# FPGA.net
KiCad netlist of a schematic drawn in Altium Designer
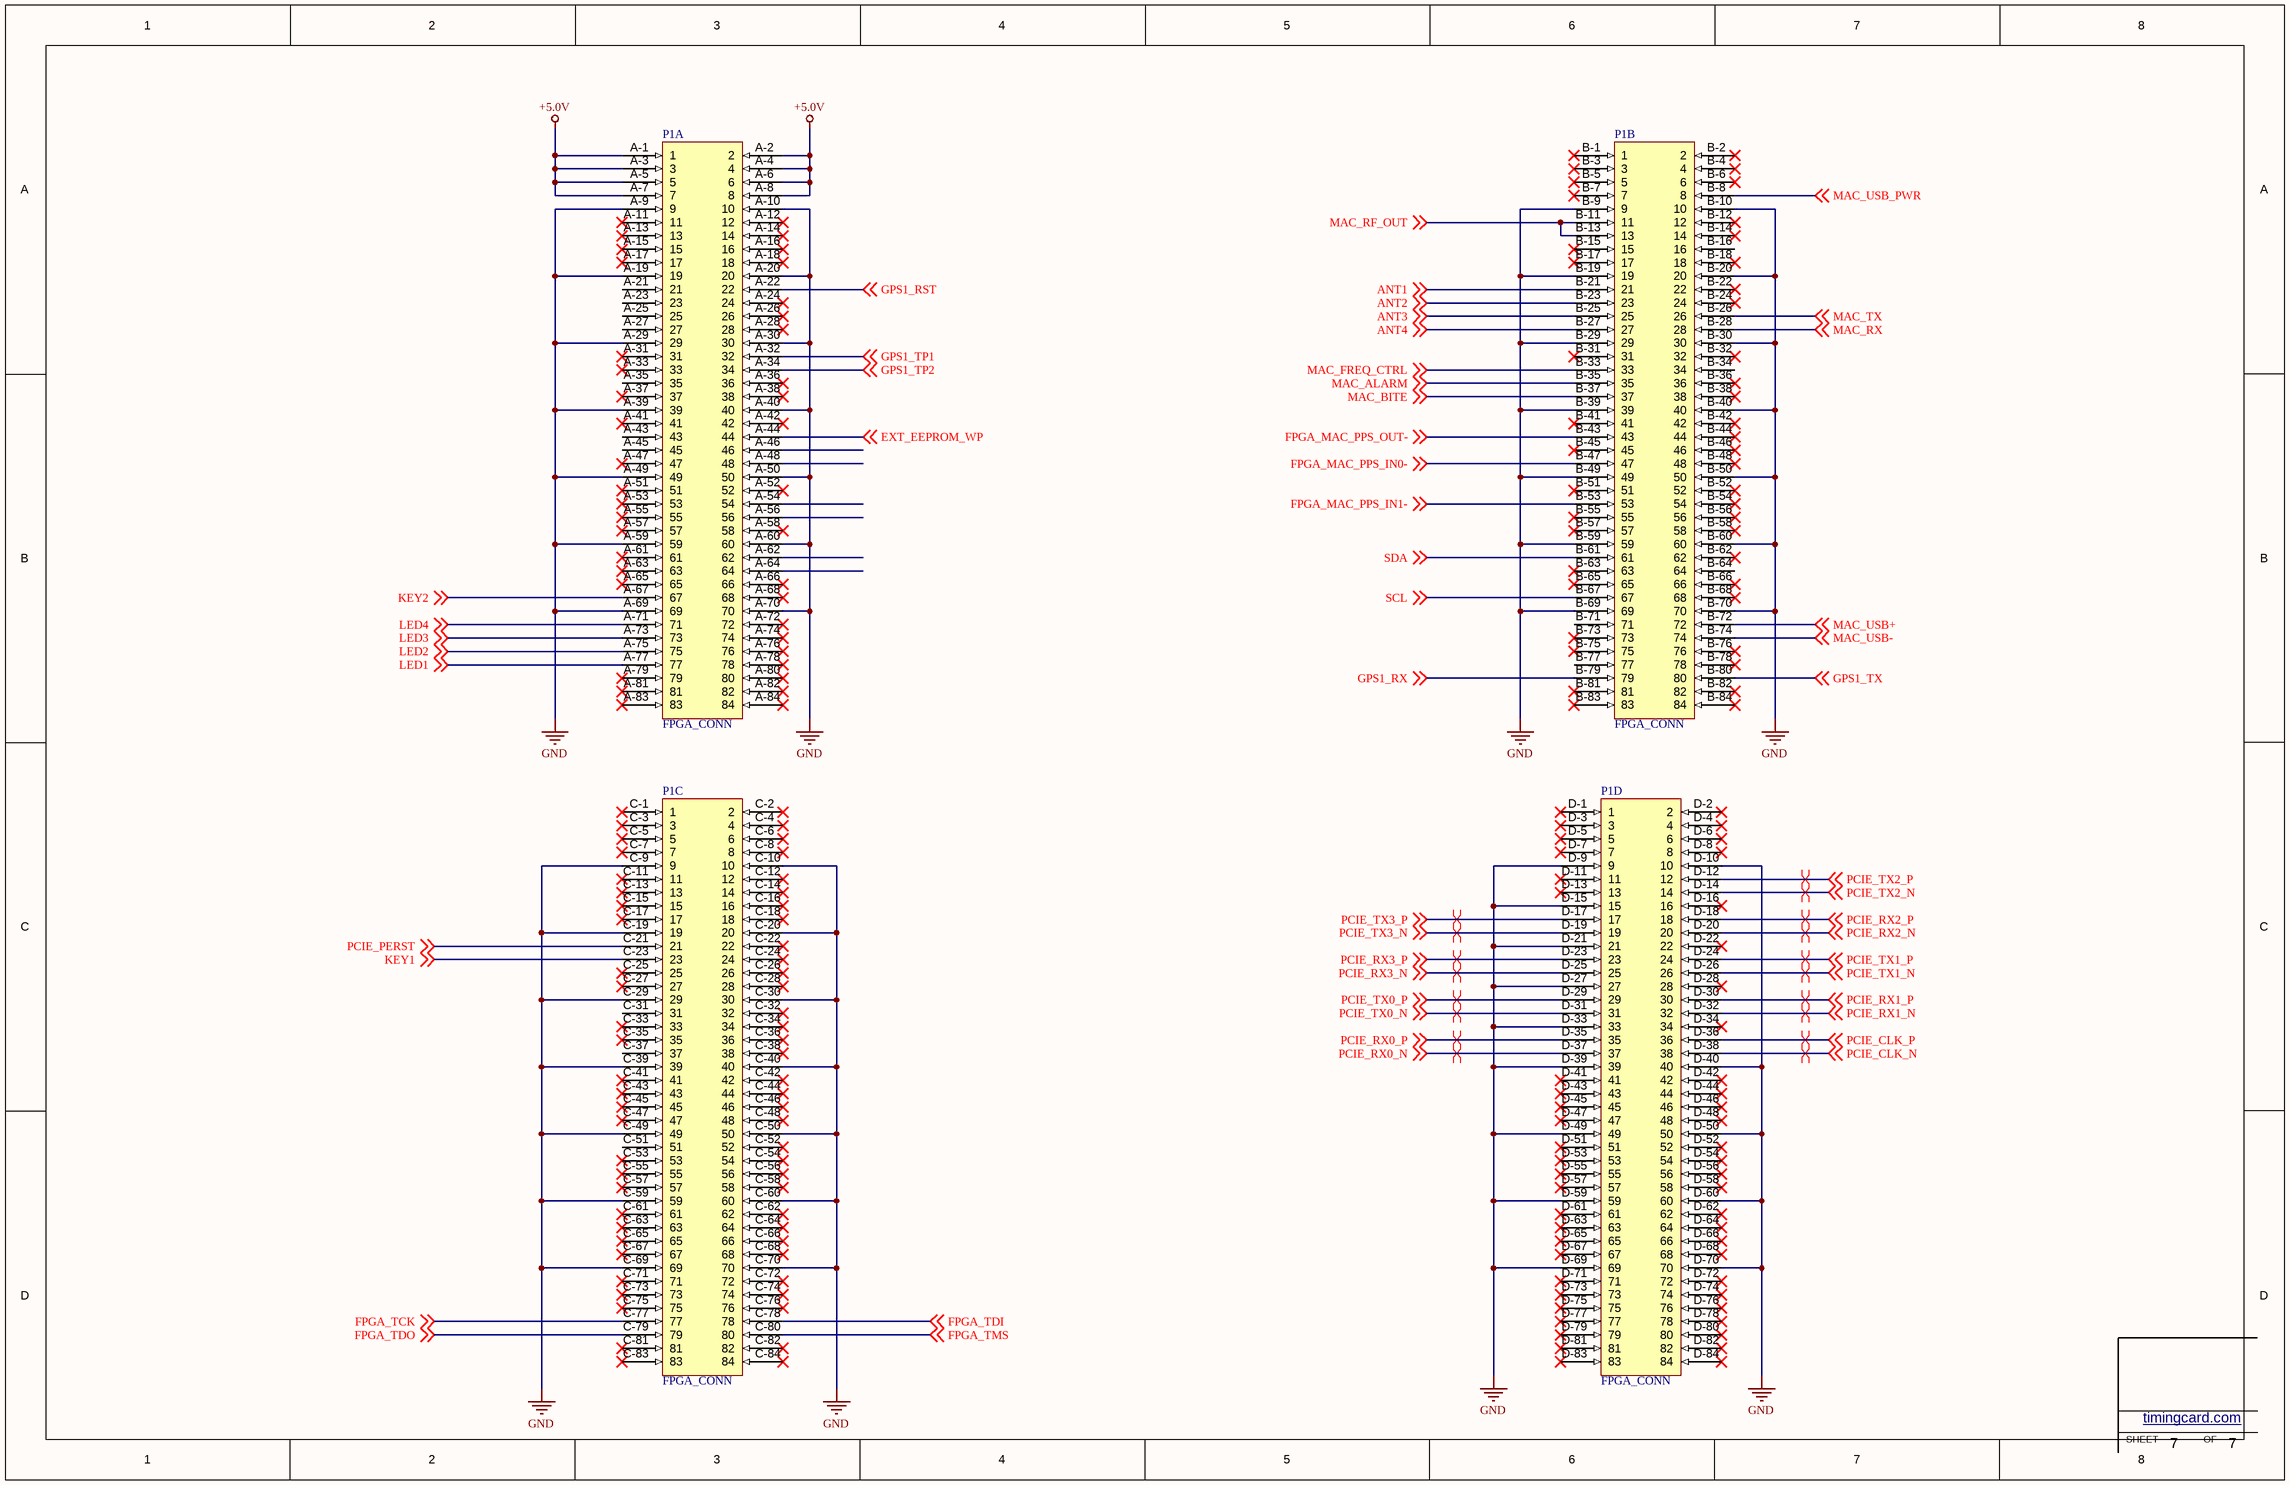
[diagram p0: FPGA.SchDoc]

(export (version "E")
  (design (tool "Eeschema 10.0.6"))
  (components
    (comp (ref "P1")
      (value "FPGA_CONN")
      (footprint "FPGA_CONN")
      (libsource (lib "FPGA_CONN") (part "FPGA_CONN"))
    )
  )
  (nets
    (net (code "1") (name "+5.0V") (class "Default")
      (node (ref "P1") (pin "A-1") (pinfunction "1_A-1") (pintype "input"))
      (node (ref "P1") (pin "A-2") (pinfunction "2_A-2") (pintype "input"))
      (node (ref "P1") (pin "A-3") (pinfunction "3_A-3") (pintype "input"))
      (node (ref "P1") (pin "A-4") (pinfunction "4_A-4") (pintype "input"))
      (node (ref "P1") (pin "A-5") (pinfunction "5_A-5") (pintype "input"))
      (node (ref "P1") (pin "A-6") (pinfunction "6_A-6") (pintype "input"))
      (node (ref "P1") (pin "A-7") (pinfunction "7_A-7") (pintype "input"))
      (node (ref "P1") (pin "A-8") (pinfunction "8_A-8") (pintype "input"))
    )
    (net (code "2") (name "ANT1") (class "Default")
      (node (ref "P1") (pin "B-21") (pinfunction "21_B-21") (pintype "input"))
    )
    (net (code "3") (name "ANT2") (class "Default")
      (node (ref "P1") (pin "B-23") (pinfunction "23_B-23") (pintype "input"))
    )
    (net (code "4") (name "ANT3") (class "Default")
      (node (ref "P1") (pin "B-25") (pinfunction "25_B-25") (pintype "input"))
    )
    (net (code "5") (name "ANT4") (class "Default")
      (node (ref "P1") (pin "B-27") (pinfunction "27_B-27") (pintype "input"))
    )
    (net (code "6") (name "EXT_EEPROM_WP") (class "Default")
      (node (ref "P1") (pin "A-44") (pinfunction "44_A-44") (pintype "input"))
    )
    (net (code "7") (name "FPGA_MAC_PPS_IN0-") (class "Default")
      (node (ref "P1") (pin "B-47") (pinfunction "47_B-47") (pintype "input"))
    )
    (net (code "8") (name "FPGA_MAC_PPS_IN1-") (class "Default")
      (node (ref "P1") (pin "B-53") (pinfunction "53_B-53") (pintype "input"))
    )
    (net (code "9") (name "FPGA_MAC_PPS_OUT-") (class "Default")
      (node (ref "P1") (pin "B-43") (pinfunction "43_B-43") (pintype "input"))
    )
    (net (code "10") (name "FPGA_TCK") (class "Default")
      (node (ref "P1") (pin "C-77") (pinfunction "77_C-77") (pintype "input"))
    )
    (net (code "11") (name "FPGA_TDI") (class "Default")
      (node (ref "P1") (pin "C-78") (pinfunction "78_C-78") (pintype "input"))
    )
    (net (code "12") (name "FPGA_TDO") (class "Default")
      (node (ref "P1") (pin "C-79") (pinfunction "79_C-79") (pintype "input"))
    )
    (net (code "13") (name "FPGA_TMS") (class "Default")
      (node (ref "P1") (pin "C-80") (pinfunction "80_C-80") (pintype "input"))
    )
    (net (code "14") (name "GND") (class "Default")
      (node (ref "P1") (pin "A-10") (pinfunction "10_A-10") (pintype "input"))
      (node (ref "P1") (pin "A-19") (pinfunction "19_A-19") (pintype "input"))
      (node (ref "P1") (pin "A-20") (pinfunction "20_A-20") (pintype "input"))
      (node (ref "P1") (pin "A-29") (pinfunction "29_A-29") (pintype "input"))
      (node (ref "P1") (pin "A-30") (pinfunction "30_A-30") (pintype "input"))
      (node (ref "P1") (pin "A-39") (pinfunction "39_A-39") (pintype "input"))
      (node (ref "P1") (pin "A-40") (pinfunction "40_A-40") (pintype "input"))
      (node (ref "P1") (pin "A-49") (pinfunction "49_A-49") (pintype "input"))
      (node (ref "P1") (pin "A-50") (pinfunction "50_A-50") (pintype "input"))
      (node (ref "P1") (pin "A-59") (pinfunction "59_A-59") (pintype "input"))
      (node (ref "P1") (pin "A-60") (pinfunction "60_A-60") (pintype "input"))
      (node (ref "P1") (pin "A-69") (pinfunction "69_A-69") (pintype "input"))
      (node (ref "P1") (pin "A-70") (pinfunction "70_A-70") (pintype "input"))
      (node (ref "P1") (pin "A-9") (pinfunction "9_A-9") (pintype "input"))
      (node (ref "P1") (pin "B-10") (pinfunction "10_B-10") (pintype "input"))
      (node (ref "P1") (pin "B-19") (pinfunction "19_B-19") (pintype "input"))
      (node (ref "P1") (pin "B-20") (pinfunction "20_B-20") (pintype "input"))
      (node (ref "P1") (pin "B-29") (pinfunction "29_B-29") (pintype "input"))
      (node (ref "P1") (pin "B-30") (pinfunction "30_B-30") (pintype "input"))
      (node (ref "P1") (pin "B-39") (pinfunction "39_B-39") (pintype "input"))
      (node (ref "P1") (pin "B-40") (pinfunction "40_B-40") (pintype "input"))
      (node (ref "P1") (pin "B-49") (pinfunction "49_B-49") (pintype "input"))
      (node (ref "P1") (pin "B-50") (pinfunction "50_B-50") (pintype "input"))
      (node (ref "P1") (pin "B-59") (pinfunction "59_B-59") (pintype "input"))
      (node (ref "P1") (pin "B-60") (pinfunction "60_B-60") (pintype "input"))
      (node (ref "P1") (pin "B-69") (pinfunction "69_B-69") (pintype "input"))
      (node (ref "P1") (pin "B-70") (pinfunction "70_B-70") (pintype "input"))
      (node (ref "P1") (pin "B-9") (pinfunction "9_B-9") (pintype "input"))
      (node (ref "P1") (pin "C-10") (pinfunction "10_C-10") (pintype "input"))
      (node (ref "P1") (pin "C-19") (pinfunction "19_C-19") (pintype "input"))
      (node (ref "P1") (pin "C-20") (pinfunction "20_C-20") (pintype "input"))
      (node (ref "P1") (pin "C-29") (pinfunction "29_C-29") (pintype "input"))
      (node (ref "P1") (pin "C-30") (pinfunction "30_C-30") (pintype "input"))
      (node (ref "P1") (pin "C-39") (pinfunction "39_C-39") (pintype "input"))
      (node (ref "P1") (pin "C-40") (pinfunction "40_C-40") (pintype "input"))
      (node (ref "P1") (pin "C-49") (pinfunction "49_C-49") (pintype "input"))
      (node (ref "P1") (pin "C-50") (pinfunction "50_C-50") (pintype "input"))
      (node (ref "P1") (pin "C-59") (pinfunction "59_C-59") (pintype "input"))
      (node (ref "P1") (pin "C-60") (pinfunction "60_C-60") (pintype "input"))
      (node (ref "P1") (pin "C-69") (pinfunction "69_C-69") (pintype "input"))
      (node (ref "P1") (pin "C-70") (pinfunction "70_C-70") (pintype "input"))
      (node (ref "P1") (pin "C-9") (pinfunction "9_C-9") (pintype "input"))
      (node (ref "P1") (pin "D-10") (pinfunction "10_D-10") (pintype "input"))
      (node (ref "P1") (pin "D-15") (pinfunction "15_D-15") (pintype "input"))
      (node (ref "P1") (pin "D-21") (pinfunction "21_D-21") (pintype "input"))
      (node (ref "P1") (pin "D-27") (pinfunction "27_D-27") (pintype "input"))
      (node (ref "P1") (pin "D-33") (pinfunction "33_D-33") (pintype "input"))
      (node (ref "P1") (pin "D-39") (pinfunction "39_D-39") (pintype "input"))
      (node (ref "P1") (pin "D-40") (pinfunction "40_D-40") (pintype "input"))
      (node (ref "P1") (pin "D-49") (pinfunction "49_D-49") (pintype "input"))
      (node (ref "P1") (pin "D-50") (pinfunction "50_D-50") (pintype "input"))
      (node (ref "P1") (pin "D-59") (pinfunction "59_D-59") (pintype "input"))
      (node (ref "P1") (pin "D-60") (pinfunction "60_D-60") (pintype "input"))
      (node (ref "P1") (pin "D-69") (pinfunction "69_D-69") (pintype "input"))
      (node (ref "P1") (pin "D-70") (pinfunction "70_D-70") (pintype "input"))
      (node (ref "P1") (pin "D-9") (pinfunction "9_D-9") (pintype "input"))
    )
    (net (code "15") (name "GPS1_RST") (class "Default")
      (node (ref "P1") (pin "A-22") (pinfunction "22_A-22") (pintype "input"))
    )
    (net (code "16") (name "GPS1_RX") (class "Default")
      (node (ref "P1") (pin "B-79") (pinfunction "79_B-79") (pintype "input"))
    )
    (net (code "17") (name "GPS1_TP1") (class "Default")
      (node (ref "P1") (pin "A-32") (pinfunction "32_A-32") (pintype "input"))
    )
    (net (code "18") (name "GPS1_TP2") (class "Default")
      (node (ref "P1") (pin "A-34") (pinfunction "34_A-34") (pintype "input"))
    )
    (net (code "19") (name "GPS1_TX") (class "Default")
      (node (ref "P1") (pin "B-80") (pinfunction "80_B-80") (pintype "input"))
    )
    (net (code "20") (name "KEY1") (class "Default")
      (node (ref "P1") (pin "C-23") (pinfunction "23_C-23") (pintype "input"))
    )
    (net (code "21") (name "KEY2") (class "Default")
      (node (ref "P1") (pin "A-67") (pinfunction "67_A-67") (pintype "input"))
    )
    (net (code "22") (name "LED1") (class "Default")
      (node (ref "P1") (pin "A-77") (pinfunction "77_A-77") (pintype "input"))
    )
    (net (code "23") (name "LED2") (class "Default")
      (node (ref "P1") (pin "A-75") (pinfunction "75_A-75") (pintype "input"))
    )
    (net (code "24") (name "LED3") (class "Default")
      (node (ref "P1") (pin "A-73") (pinfunction "73_A-73") (pintype "input"))
    )
    (net (code "25") (name "LED4") (class "Default")
      (node (ref "P1") (pin "A-71") (pinfunction "71_A-71") (pintype "input"))
    )
    (net (code "26") (name "MAC_ALARM") (class "Default")
      (node (ref "P1") (pin "B-35") (pinfunction "35_B-35") (pintype "input"))
    )
    (net (code "27") (name "MAC_BITE") (class "Default")
      (node (ref "P1") (pin "B-37") (pinfunction "37_B-37") (pintype "input"))
    )
    (net (code "28") (name "MAC_FREQ_CTRL") (class "Default")
      (node (ref "P1") (pin "B-33") (pinfunction "33_B-33") (pintype "input"))
    )
    (net (code "29") (name "MAC_RF_OUT") (class "Default")
      (node (ref "P1") (pin "B-11") (pinfunction "11_B-11") (pintype "input"))
      (node (ref "P1") (pin "B-13") (pinfunction "13_B-13") (pintype "input"))
    )
    (net (code "30") (name "MAC_RX") (class "Default")
      (node (ref "P1") (pin "B-28") (pinfunction "28_B-28") (pintype "input"))
    )
    (net (code "31") (name "MAC_TX") (class "Default")
      (node (ref "P1") (pin "B-26") (pinfunction "26_B-26") (pintype "input"))
    )
    (net (code "32") (name "MAC_USB+") (class "Default")
      (node (ref "P1") (pin "B-72") (pinfunction "72_B-72") (pintype "input"))
    )
    (net (code "33") (name "MAC_USB-") (class "Default")
      (node (ref "P1") (pin "B-74") (pinfunction "74_B-74") (pintype "input"))
    )
    (net (code "34") (name "MAC_USB_PWR") (class "Default")
      (node (ref "P1") (pin "B-8") (pinfunction "8_B-8") (pintype "input"))
    )
    (net (code "35") (name "PCIE_CLK_N") (class "Default")
      (node (ref "P1") (pin "D-38") (pinfunction "38_D-38") (pintype "input"))
    )
    (net (code "36") (name "PCIE_CLK_P") (class "Default")
      (node (ref "P1") (pin "D-36") (pinfunction "36_D-36") (pintype "input"))
    )
    (net (code "37") (name "PCIE_PERST") (class "Default")
      (node (ref "P1") (pin "C-21") (pinfunction "21_C-21") (pintype "input"))
    )
    (net (code "38") (name "PCIE_RX0_N") (class "Default")
      (node (ref "P1") (pin "D-37") (pinfunction "37_D-37") (pintype "input"))
    )
    (net (code "39") (name "PCIE_RX0_P") (class "Default")
      (node (ref "P1") (pin "D-35") (pinfunction "35_D-35") (pintype "input"))
    )
    (net (code "40") (name "PCIE_RX1_N") (class "Default")
      (node (ref "P1") (pin "D-32") (pinfunction "32_D-32") (pintype "input"))
    )
    (net (code "41") (name "PCIE_RX1_P") (class "Default")
      (node (ref "P1") (pin "D-30") (pinfunction "30_D-30") (pintype "input"))
    )
    (net (code "42") (name "PCIE_RX2_N") (class "Default")
      (node (ref "P1") (pin "D-20") (pinfunction "20_D-20") (pintype "input"))
    )
    (net (code "43") (name "PCIE_RX2_P") (class "Default")
      (node (ref "P1") (pin "D-18") (pinfunction "18_D-18") (pintype "input"))
    )
    (net (code "44") (name "PCIE_RX3_N") (class "Default")
      (node (ref "P1") (pin "D-25") (pinfunction "25_D-25") (pintype "input"))
    )
    (net (code "45") (name "PCIE_RX3_P") (class "Default")
      (node (ref "P1") (pin "D-23") (pinfunction "23_D-23") (pintype "input"))
    )
    (net (code "46") (name "PCIE_TX0_N") (class "Default")
      (node (ref "P1") (pin "D-31") (pinfunction "31_D-31") (pintype "input"))
    )
    (net (code "47") (name "PCIE_TX0_P") (class "Default")
      (node (ref "P1") (pin "D-29") (pinfunction "29_D-29") (pintype "input"))
    )
    (net (code "48") (name "PCIE_TX1_N") (class "Default")
      (node (ref "P1") (pin "D-26") (pinfunction "26_D-26") (pintype "input"))
    )
    (net (code "49") (name "PCIE_TX1_P") (class "Default")
      (node (ref "P1") (pin "D-24") (pinfunction "24_D-24") (pintype "input"))
    )
    (net (code "50") (name "PCIE_TX2_N") (class "Default")
      (node (ref "P1") (pin "D-14") (pinfunction "14_D-14") (pintype "input"))
    )
    (net (code "51") (name "PCIE_TX2_P") (class "Default")
      (node (ref "P1") (pin "D-12") (pinfunction "12_D-12") (pintype "input"))
    )
    (net (code "52") (name "PCIE_TX3_N") (class "Default")
      (node (ref "P1") (pin "D-19") (pinfunction "19_D-19") (pintype "input"))
    )
    (net (code "53") (name "PCIE_TX3_P") (class "Default")
      (node (ref "P1") (pin "D-17") (pinfunction "17_D-17") (pintype "input"))
    )
    (net (code "54") (name "SCL") (class "Default")
      (node (ref "P1") (pin "B-67") (pinfunction "67_B-67") (pintype "input"))
    )
    (net (code "55") (name "SDA") (class "Default")
      (node (ref "P1") (pin "B-61") (pinfunction "61_B-61") (pintype "input"))
    )
    (net (code "56") (name "unconnected-(P1A-11-PadA-11)") (class "Default")
      (node (ref "P1") (pin "A-11") (pinfunction "11_A-11") (pintype "input+no_connect"))
    )
    (net (code "57") (name "unconnected-(P1A-12-PadA-12)") (class "Default")
      (node (ref "P1") (pin "A-12") (pinfunction "12_A-12") (pintype "input+no_connect"))
    )
    (net (code "58") (name "unconnected-(P1A-13-PadA-13)") (class "Default")
      (node (ref "P1") (pin "A-13") (pinfunction "13_A-13") (pintype "input+no_connect"))
    )
    (net (code "59") (name "unconnected-(P1A-14-PadA-14)") (class "Default")
      (node (ref "P1") (pin "A-14") (pinfunction "14_A-14") (pintype "input+no_connect"))
    )
    (net (code "60") (name "unconnected-(P1A-15-PadA-15)") (class "Default")
      (node (ref "P1") (pin "A-15") (pinfunction "15_A-15") (pintype "input+no_connect"))
    )
    (net (code "61") (name "unconnected-(P1A-16-PadA-16)") (class "Default")
      (node (ref "P1") (pin "A-16") (pinfunction "16_A-16") (pintype "input+no_connect"))
    )
    (net (code "62") (name "unconnected-(P1A-17-PadA-17)") (class "Default")
      (node (ref "P1") (pin "A-17") (pinfunction "17_A-17") (pintype "input+no_connect"))
    )
    (net (code "63") (name "unconnected-(P1A-18-PadA-18)") (class "Default")
      (node (ref "P1") (pin "A-18") (pinfunction "18_A-18") (pintype "input+no_connect"))
    )
    (net (code "64") (name "unconnected-(P1A-21-PadA-21)") (class "Default")
      (node (ref "P1") (pin "A-21") (pinfunction "21_A-21") (pintype "input"))
    )
    (net (code "65") (name "unconnected-(P1A-23-PadA-23)") (class "Default")
      (node (ref "P1") (pin "A-23") (pinfunction "23_A-23") (pintype "input"))
    )
    (net (code "66") (name "unconnected-(P1A-24-PadA-24)") (class "Default")
      (node (ref "P1") (pin "A-24") (pinfunction "24_A-24") (pintype "input+no_connect"))
    )
    (net (code "67") (name "unconnected-(P1A-25-PadA-25)") (class "Default")
      (node (ref "P1") (pin "A-25") (pinfunction "25_A-25") (pintype "input"))
    )
    (net (code "68") (name "unconnected-(P1A-26-PadA-26)") (class "Default")
      (node (ref "P1") (pin "A-26") (pinfunction "26_A-26") (pintype "input+no_connect"))
    )
    (net (code "69") (name "unconnected-(P1A-27-PadA-27)") (class "Default")
      (node (ref "P1") (pin "A-27") (pinfunction "27_A-27") (pintype "input"))
    )
    (net (code "70") (name "unconnected-(P1A-28-PadA-28)") (class "Default")
      (node (ref "P1") (pin "A-28") (pinfunction "28_A-28") (pintype "input+no_connect"))
    )
    (net (code "71") (name "unconnected-(P1A-31-PadA-31)") (class "Default")
      (node (ref "P1") (pin "A-31") (pinfunction "31_A-31") (pintype "input+no_connect"))
    )
    (net (code "72") (name "unconnected-(P1A-33-PadA-33)") (class "Default")
      (node (ref "P1") (pin "A-33") (pinfunction "33_A-33") (pintype "input+no_connect"))
    )
    (net (code "73") (name "unconnected-(P1A-35-PadA-35)") (class "Default")
      (node (ref "P1") (pin "A-35") (pinfunction "35_A-35") (pintype "input"))
    )
    (net (code "74") (name "unconnected-(P1A-36-PadA-36)") (class "Default")
      (node (ref "P1") (pin "A-36") (pinfunction "36_A-36") (pintype "input+no_connect"))
    )
    (net (code "75") (name "unconnected-(P1A-37-PadA-37)") (class "Default")
      (node (ref "P1") (pin "A-37") (pinfunction "37_A-37") (pintype "input+no_connect"))
    )
    (net (code "76") (name "unconnected-(P1A-38-PadA-38)") (class "Default")
      (node (ref "P1") (pin "A-38") (pinfunction "38_A-38") (pintype "input+no_connect"))
    )
    (net (code "77") (name "unconnected-(P1A-41-PadA-41)") (class "Default")
      (node (ref "P1") (pin "A-41") (pinfunction "41_A-41") (pintype "input+no_connect"))
    )
    (net (code "78") (name "unconnected-(P1A-42-PadA-42)") (class "Default")
      (node (ref "P1") (pin "A-42") (pinfunction "42_A-42") (pintype "input+no_connect"))
    )
    (net (code "79") (name "unconnected-(P1A-43-PadA-43)") (class "Default")
      (node (ref "P1") (pin "A-43") (pinfunction "43_A-43") (pintype "input"))
    )
    (net (code "80") (name "unconnected-(P1A-45-PadA-45)") (class "Default")
      (node (ref "P1") (pin "A-45") (pinfunction "45_A-45") (pintype "input"))
    )
    (net (code "81") (name "unconnected-(P1A-46-PadA-46)") (class "Default")
      (node (ref "P1") (pin "A-46") (pinfunction "46_A-46") (pintype "input"))
    )
    (net (code "82") (name "unconnected-(P1A-47-PadA-47)") (class "Default")
      (node (ref "P1") (pin "A-47") (pinfunction "47_A-47") (pintype "input+no_connect"))
    )
    (net (code "83") (name "unconnected-(P1A-48-PadA-48)") (class "Default")
      (node (ref "P1") (pin "A-48") (pinfunction "48_A-48") (pintype "input"))
    )
    (net (code "84") (name "unconnected-(P1A-51-PadA-51)") (class "Default")
      (node (ref "P1") (pin "A-51") (pinfunction "51_A-51") (pintype "input+no_connect"))
    )
    (net (code "85") (name "unconnected-(P1A-52-PadA-52)") (class "Default")
      (node (ref "P1") (pin "A-52") (pinfunction "52_A-52") (pintype "input+no_connect"))
    )
    (net (code "86") (name "unconnected-(P1A-53-PadA-53)") (class "Default")
      (node (ref "P1") (pin "A-53") (pinfunction "53_A-53") (pintype "input+no_connect"))
    )
    (net (code "87") (name "unconnected-(P1A-54-PadA-54)") (class "Default")
      (node (ref "P1") (pin "A-54") (pinfunction "54_A-54") (pintype "input"))
    )
    (net (code "88") (name "unconnected-(P1A-55-PadA-55)") (class "Default")
      (node (ref "P1") (pin "A-55") (pinfunction "55_A-55") (pintype "input+no_connect"))
    )
    (net (code "89") (name "unconnected-(P1A-56-PadA-56)") (class "Default")
      (node (ref "P1") (pin "A-56") (pinfunction "56_A-56") (pintype "input"))
    )
    (net (code "90") (name "unconnected-(P1A-57-PadA-57)") (class "Default")
      (node (ref "P1") (pin "A-57") (pinfunction "57_A-57") (pintype "input+no_connect"))
    )
    (net (code "91") (name "unconnected-(P1A-58-PadA-58)") (class "Default")
      (node (ref "P1") (pin "A-58") (pinfunction "58_A-58") (pintype "input+no_connect"))
    )
    (net (code "92") (name "unconnected-(P1A-61-PadA-61)") (class "Default")
      (node (ref "P1") (pin "A-61") (pinfunction "61_A-61") (pintype "input+no_connect"))
    )
    (net (code "93") (name "unconnected-(P1A-62-PadA-62)") (class "Default")
      (node (ref "P1") (pin "A-62") (pinfunction "62_A-62") (pintype "input"))
    )
    (net (code "94") (name "unconnected-(P1A-63-PadA-63)") (class "Default")
      (node (ref "P1") (pin "A-63") (pinfunction "63_A-63") (pintype "input+no_connect"))
    )
    (net (code "95") (name "unconnected-(P1A-64-PadA-64)") (class "Default")
      (node (ref "P1") (pin "A-64") (pinfunction "64_A-64") (pintype "input"))
    )
    (net (code "96") (name "unconnected-(P1A-65-PadA-65)") (class "Default")
      (node (ref "P1") (pin "A-65") (pinfunction "65_A-65") (pintype "input+no_connect"))
    )
    (net (code "97") (name "unconnected-(P1A-66-PadA-66)") (class "Default")
      (node (ref "P1") (pin "A-66") (pinfunction "66_A-66") (pintype "input+no_connect"))
    )
    (net (code "98") (name "unconnected-(P1A-68-PadA-68)") (class "Default")
      (node (ref "P1") (pin "A-68") (pinfunction "68_A-68") (pintype "input+no_connect"))
    )
    (net (code "99") (name "unconnected-(P1A-72-PadA-72)") (class "Default")
      (node (ref "P1") (pin "A-72") (pinfunction "72_A-72") (pintype "input+no_connect"))
    )
    (net (code "100") (name "unconnected-(P1A-74-PadA-74)") (class "Default")
      (node (ref "P1") (pin "A-74") (pinfunction "74_A-74") (pintype "input+no_connect"))
    )
    (net (code "101") (name "unconnected-(P1A-76-PadA-76)") (class "Default")
      (node (ref "P1") (pin "A-76") (pinfunction "76_A-76") (pintype "input+no_connect"))
    )
    (net (code "102") (name "unconnected-(P1A-78-PadA-78)") (class "Default")
      (node (ref "P1") (pin "A-78") (pinfunction "78_A-78") (pintype "input+no_connect"))
    )
    (net (code "103") (name "unconnected-(P1A-79-PadA-79)") (class "Default")
      (node (ref "P1") (pin "A-79") (pinfunction "79_A-79") (pintype "input+no_connect"))
    )
    (net (code "104") (name "unconnected-(P1A-80-PadA-80)") (class "Default")
      (node (ref "P1") (pin "A-80") (pinfunction "80_A-80") (pintype "input+no_connect"))
    )
    (net (code "105") (name "unconnected-(P1A-81-PadA-81)") (class "Default")
      (node (ref "P1") (pin "A-81") (pinfunction "81_A-81") (pintype "input+no_connect"))
    )
    (net (code "106") (name "unconnected-(P1A-82-PadA-82)") (class "Default")
      (node (ref "P1") (pin "A-82") (pinfunction "82_A-82") (pintype "input+no_connect"))
    )
    (net (code "107") (name "unconnected-(P1A-83-PadA-83)") (class "Default")
      (node (ref "P1") (pin "A-83") (pinfunction "83_A-83") (pintype "input+no_connect"))
    )
    (net (code "108") (name "unconnected-(P1A-84-PadA-84)") (class "Default")
      (node (ref "P1") (pin "A-84") (pinfunction "84_A-84") (pintype "input+no_connect"))
    )
    (net (code "109") (name "unconnected-(P1B-1-PadB-1)") (class "Default")
      (node (ref "P1") (pin "B-1") (pinfunction "1_B-1") (pintype "input+no_connect"))
    )
    (net (code "110") (name "unconnected-(P1B-2-PadB-2)") (class "Default")
      (node (ref "P1") (pin "B-2") (pinfunction "2_B-2") (pintype "input+no_connect"))
    )
    (net (code "111") (name "unconnected-(P1B-3-PadB-3)") (class "Default")
      (node (ref "P1") (pin "B-3") (pinfunction "3_B-3") (pintype "input+no_connect"))
    )
    (net (code "112") (name "unconnected-(P1B-4-PadB-4)") (class "Default")
      (node (ref "P1") (pin "B-4") (pinfunction "4_B-4") (pintype "input+no_connect"))
    )
    (net (code "113") (name "unconnected-(P1B-5-PadB-5)") (class "Default")
      (node (ref "P1") (pin "B-5") (pinfunction "5_B-5") (pintype "input+no_connect"))
    )
    (net (code "114") (name "unconnected-(P1B-6-PadB-6)") (class "Default")
      (node (ref "P1") (pin "B-6") (pinfunction "6_B-6") (pintype "input+no_connect"))
    )
    (net (code "115") (name "unconnected-(P1B-7-PadB-7)") (class "Default")
      (node (ref "P1") (pin "B-7") (pinfunction "7_B-7") (pintype "input+no_connect"))
    )
    (net (code "116") (name "unconnected-(P1B-12-PadB-12)") (class "Default")
      (node (ref "P1") (pin "B-12") (pinfunction "12_B-12") (pintype "input+no_connect"))
    )
    (net (code "117") (name "unconnected-(P1B-14-PadB-14)") (class "Default")
      (node (ref "P1") (pin "B-14") (pinfunction "14_B-14") (pintype "input+no_connect"))
    )
    (net (code "118") (name "unconnected-(P1B-15-PadB-15)") (class "Default")
      (node (ref "P1") (pin "B-15") (pinfunction "15_B-15") (pintype "input+no_connect"))
    )
    (net (code "119") (name "unconnected-(P1B-16-PadB-16)") (class "Default")
      (node (ref "P1") (pin "B-16") (pinfunction "16_B-16") (pintype "input"))
    )
    (net (code "120") (name "unconnected-(P1B-17-PadB-17)") (class "Default")
      (node (ref "P1") (pin "B-17") (pinfunction "17_B-17") (pintype "input+no_connect"))
    )
    (net (code "121") (name "unconnected-(P1B-18-PadB-18)") (class "Default")
      (node (ref "P1") (pin "B-18") (pinfunction "18_B-18") (pintype "input+no_connect"))
    )
    (net (code "122") (name "unconnected-(P1B-22-PadB-22)") (class "Default")
      (node (ref "P1") (pin "B-22") (pinfunction "22_B-22") (pintype "input+no_connect"))
    )
    (net (code "123") (name "unconnected-(P1B-24-PadB-24)") (class "Default")
      (node (ref "P1") (pin "B-24") (pinfunction "24_B-24") (pintype "input+no_connect"))
    )
    (net (code "124") (name "unconnected-(P1B-31-PadB-31)") (class "Default")
      (node (ref "P1") (pin "B-31") (pinfunction "31_B-31") (pintype "input+no_connect"))
    )
    (net (code "125") (name "unconnected-(P1B-32-PadB-32)") (class "Default")
      (node (ref "P1") (pin "B-32") (pinfunction "32_B-32") (pintype "input+no_connect"))
    )
    (net (code "126") (name "unconnected-(P1B-34-PadB-34)") (class "Default")
      (node (ref "P1") (pin "B-34") (pinfunction "34_B-34") (pintype "input"))
    )
    (net (code "127") (name "unconnected-(P1B-36-PadB-36)") (class "Default")
      (node (ref "P1") (pin "B-36") (pinfunction "36_B-36") (pintype "input+no_connect"))
    )
    (net (code "128") (name "unconnected-(P1B-38-PadB-38)") (class "Default")
      (node (ref "P1") (pin "B-38") (pinfunction "38_B-38") (pintype "input+no_connect"))
    )
    (net (code "129") (name "unconnected-(P1B-41-PadB-41)") (class "Default")
      (node (ref "P1") (pin "B-41") (pinfunction "41_B-41") (pintype "input+no_connect"))
    )
    (net (code "130") (name "unconnected-(P1B-42-PadB-42)") (class "Default")
      (node (ref "P1") (pin "B-42") (pinfunction "42_B-42") (pintype "input+no_connect"))
    )
    (net (code "131") (name "unconnected-(P1B-44-PadB-44)") (class "Default")
      (node (ref "P1") (pin "B-44") (pinfunction "44_B-44") (pintype "input+no_connect"))
    )
    (net (code "132") (name "unconnected-(P1B-45-PadB-45)") (class "Default")
      (node (ref "P1") (pin "B-45") (pinfunction "45_B-45") (pintype "input+no_connect"))
    )
    (net (code "133") (name "unconnected-(P1B-46-PadB-46)") (class "Default")
      (node (ref "P1") (pin "B-46") (pinfunction "46_B-46") (pintype "input+no_connect"))
    )
    (net (code "134") (name "unconnected-(P1B-48-PadB-48)") (class "Default")
      (node (ref "P1") (pin "B-48") (pinfunction "48_B-48") (pintype "input+no_connect"))
    )
    (net (code "135") (name "unconnected-(P1B-51-PadB-51)") (class "Default")
      (node (ref "P1") (pin "B-51") (pinfunction "51_B-51") (pintype "input+no_connect"))
    )
    (net (code "136") (name "unconnected-(P1B-52-PadB-52)") (class "Default")
      (node (ref "P1") (pin "B-52") (pinfunction "52_B-52") (pintype "input+no_connect"))
    )
    (net (code "137") (name "unconnected-(P1B-54-PadB-54)") (class "Default")
      (node (ref "P1") (pin "B-54") (pinfunction "54_B-54") (pintype "input+no_connect"))
    )
    (net (code "138") (name "unconnected-(P1B-55-PadB-55)") (class "Default")
      (node (ref "P1") (pin "B-55") (pinfunction "55_B-55") (pintype "input+no_connect"))
    )
    (net (code "139") (name "unconnected-(P1B-56-PadB-56)") (class "Default")
      (node (ref "P1") (pin "B-56") (pinfunction "56_B-56") (pintype "input+no_connect"))
    )
    (net (code "140") (name "unconnected-(P1B-57-PadB-57)") (class "Default")
      (node (ref "P1") (pin "B-57") (pinfunction "57_B-57") (pintype "input+no_connect"))
    )
    (net (code "141") (name "unconnected-(P1B-58-PadB-58)") (class "Default")
      (node (ref "P1") (pin "B-58") (pinfunction "58_B-58") (pintype "input+no_connect"))
    )
    (net (code "142") (name "unconnected-(P1B-62-PadB-62)") (class "Default")
      (node (ref "P1") (pin "B-62") (pinfunction "62_B-62") (pintype "input+no_connect"))
    )
    (net (code "143") (name "unconnected-(P1B-63-PadB-63)") (class "Default")
      (node (ref "P1") (pin "B-63") (pinfunction "63_B-63") (pintype "input+no_connect"))
    )
    (net (code "144") (name "unconnected-(P1B-64-PadB-64)") (class "Default")
      (node (ref "P1") (pin "B-64") (pinfunction "64_B-64") (pintype "input"))
    )
    (net (code "145") (name "unconnected-(P1B-65-PadB-65)") (class "Default")
      (node (ref "P1") (pin "B-65") (pinfunction "65_B-65") (pintype "input+no_connect"))
    )
    (net (code "146") (name "unconnected-(P1B-66-PadB-66)") (class "Default")
      (node (ref "P1") (pin "B-66") (pinfunction "66_B-66") (pintype "input+no_connect"))
    )
    (net (code "147") (name "unconnected-(P1B-68-PadB-68)") (class "Default")
      (node (ref "P1") (pin "B-68") (pinfunction "68_B-68") (pintype "input+no_connect"))
    )
    (net (code "148") (name "unconnected-(P1B-71-PadB-71)") (class "Default")
      (node (ref "P1") (pin "B-71") (pinfunction "71_B-71") (pintype "input"))
    )
    (net (code "149") (name "unconnected-(P1B-73-PadB-73)") (class "Default")
      (node (ref "P1") (pin "B-73") (pinfunction "73_B-73") (pintype "input+no_connect"))
    )
    (net (code "150") (name "unconnected-(P1B-75-PadB-75)") (class "Default")
      (node (ref "P1") (pin "B-75") (pinfunction "75_B-75") (pintype "input+no_connect"))
    )
    (net (code "151") (name "unconnected-(P1B-76-PadB-76)") (class "Default")
      (node (ref "P1") (pin "B-76") (pinfunction "76_B-76") (pintype "input+no_connect"))
    )
    (net (code "152") (name "unconnected-(P1B-77-PadB-77)") (class "Default")
      (node (ref "P1") (pin "B-77") (pinfunction "77_B-77") (pintype "input"))
    )
    (net (code "153") (name "unconnected-(P1B-78-PadB-78)") (class "Default")
      (node (ref "P1") (pin "B-78") (pinfunction "78_B-78") (pintype "input+no_connect"))
    )
    (net (code "154") (name "unconnected-(P1B-81-PadB-81)") (class "Default")
      (node (ref "P1") (pin "B-81") (pinfunction "81_B-81") (pintype "input+no_connect"))
    )
    (net (code "155") (name "unconnected-(P1B-82-PadB-82)") (class "Default")
      (node (ref "P1") (pin "B-82") (pinfunction "82_B-82") (pintype "input+no_connect"))
    )
    (net (code "156") (name "unconnected-(P1B-83-PadB-83)") (class "Default")
      (node (ref "P1") (pin "B-83") (pinfunction "83_B-83") (pintype "input+no_connect"))
    )
    (net (code "157") (name "unconnected-(P1B-84-PadB-84)") (class "Default")
      (node (ref "P1") (pin "B-84") (pinfunction "84_B-84") (pintype "input+no_connect"))
    )
    (net (code "158") (name "unconnected-(P1C-1-PadC-1)") (class "Default")
      (node (ref "P1") (pin "C-1") (pinfunction "1_C-1") (pintype "input+no_connect"))
    )
    (net (code "159") (name "unconnected-(P1C-2-PadC-2)") (class "Default")
      (node (ref "P1") (pin "C-2") (pinfunction "2_C-2") (pintype "input+no_connect"))
    )
    (net (code "160") (name "unconnected-(P1C-3-PadC-3)") (class "Default")
      (node (ref "P1") (pin "C-3") (pinfunction "3_C-3") (pintype "input+no_connect"))
    )
    (net (code "161") (name "unconnected-(P1C-4-PadC-4)") (class "Default")
      (node (ref "P1") (pin "C-4") (pinfunction "4_C-4") (pintype "input+no_connect"))
    )
    (net (code "162") (name "unconnected-(P1C-5-PadC-5)") (class "Default")
      (node (ref "P1") (pin "C-5") (pinfunction "5_C-5") (pintype "input+no_connect"))
    )
    (net (code "163") (name "unconnected-(P1C-6-PadC-6)") (class "Default")
      (node (ref "P1") (pin "C-6") (pinfunction "6_C-6") (pintype "input+no_connect"))
    )
    (net (code "164") (name "unconnected-(P1C-7-PadC-7)") (class "Default")
      (node (ref "P1") (pin "C-7") (pinfunction "7_C-7") (pintype "input+no_connect"))
    )
    (net (code "165") (name "unconnected-(P1C-8-PadC-8)") (class "Default")
      (node (ref "P1") (pin "C-8") (pinfunction "8_C-8") (pintype "input+no_connect"))
    )
    (net (code "166") (name "unconnected-(P1C-11-PadC-11)") (class "Default")
      (node (ref "P1") (pin "C-11") (pinfunction "11_C-11") (pintype "input+no_connect"))
    )
    (net (code "167") (name "unconnected-(P1C-12-PadC-12)") (class "Default")
      (node (ref "P1") (pin "C-12") (pinfunction "12_C-12") (pintype "input+no_connect"))
    )
    (net (code "168") (name "unconnected-(P1C-13-PadC-13)") (class "Default")
      (node (ref "P1") (pin "C-13") (pinfunction "13_C-13") (pintype "input+no_connect"))
    )
    (net (code "169") (name "unconnected-(P1C-14-PadC-14)") (class "Default")
      (node (ref "P1") (pin "C-14") (pinfunction "14_C-14") (pintype "input+no_connect"))
    )
    (net (code "170") (name "unconnected-(P1C-15-PadC-15)") (class "Default")
      (node (ref "P1") (pin "C-15") (pinfunction "15_C-15") (pintype "input+no_connect"))
    )
    (net (code "171") (name "unconnected-(P1C-16-PadC-16)") (class "Default")
      (node (ref "P1") (pin "C-16") (pinfunction "16_C-16") (pintype "input+no_connect"))
    )
    (net (code "172") (name "unconnected-(P1C-17-PadC-17)") (class "Default")
      (node (ref "P1") (pin "C-17") (pinfunction "17_C-17") (pintype "input+no_connect"))
    )
    (net (code "173") (name "unconnected-(P1C-18-PadC-18)") (class "Default")
      (node (ref "P1") (pin "C-18") (pinfunction "18_C-18") (pintype "input+no_connect"))
    )
    (net (code "174") (name "unconnected-(P1C-22-PadC-22)") (class "Default")
      (node (ref "P1") (pin "C-22") (pinfunction "22_C-22") (pintype "input+no_connect"))
    )
    (net (code "175") (name "unconnected-(P1C-24-PadC-24)") (class "Default")
      (node (ref "P1") (pin "C-24") (pinfunction "24_C-24") (pintype "input+no_connect"))
    )
    (net (code "176") (name "unconnected-(P1C-25-PadC-25)") (class "Default")
      (node (ref "P1") (pin "C-25") (pinfunction "25_C-25") (pintype "input+no_connect"))
    )
    (net (code "177") (name "unconnected-(P1C-26-PadC-26)") (class "Default")
      (node (ref "P1") (pin "C-26") (pinfunction "26_C-26") (pintype "input+no_connect"))
    )
    (net (code "178") (name "unconnected-(P1C-27-PadC-27)") (class "Default")
      (node (ref "P1") (pin "C-27") (pinfunction "27_C-27") (pintype "input+no_connect"))
    )
    (net (code "179") (name "unconnected-(P1C-28-PadC-28)") (class "Default")
      (node (ref "P1") (pin "C-28") (pinfunction "28_C-28") (pintype "input+no_connect"))
    )
    (net (code "180") (name "unconnected-(P1C-31-PadC-31)") (class "Default")
      (node (ref "P1") (pin "C-31") (pinfunction "31_C-31") (pintype "input"))
    )
    (net (code "181") (name "unconnected-(P1C-32-PadC-32)") (class "Default")
      (node (ref "P1") (pin "C-32") (pinfunction "32_C-32") (pintype "input+no_connect"))
    )
    (net (code "182") (name "unconnected-(P1C-33-PadC-33)") (class "Default")
      (node (ref "P1") (pin "C-33") (pinfunction "33_C-33") (pintype "input+no_connect"))
    )
    (net (code "183") (name "unconnected-(P1C-34-PadC-34)") (class "Default")
      (node (ref "P1") (pin "C-34") (pinfunction "34_C-34") (pintype "input+no_connect"))
    )
    (net (code "184") (name "unconnected-(P1C-35-PadC-35)") (class "Default")
      (node (ref "P1") (pin "C-35") (pinfunction "35_C-35") (pintype "input+no_connect"))
    )
    (net (code "185") (name "unconnected-(P1C-36-PadC-36)") (class "Default")
      (node (ref "P1") (pin "C-36") (pinfunction "36_C-36") (pintype "input+no_connect"))
    )
    (net (code "186") (name "unconnected-(P1C-37-PadC-37)") (class "Default")
      (node (ref "P1") (pin "C-37") (pinfunction "37_C-37") (pintype "input"))
    )
    (net (code "187") (name "unconnected-(P1C-38-PadC-38)") (class "Default")
      (node (ref "P1") (pin "C-38") (pinfunction "38_C-38") (pintype "input+no_connect"))
    )
    (net (code "188") (name "unconnected-(P1C-41-PadC-41)") (class "Default")
      (node (ref "P1") (pin "C-41") (pinfunction "41_C-41") (pintype "input+no_connect"))
    )
    (net (code "189") (name "unconnected-(P1C-42-PadC-42)") (class "Default")
      (node (ref "P1") (pin "C-42") (pinfunction "42_C-42") (pintype "input+no_connect"))
    )
    (net (code "190") (name "unconnected-(P1C-43-PadC-43)") (class "Default")
      (node (ref "P1") (pin "C-43") (pinfunction "43_C-43") (pintype "input+no_connect"))
    )
    (net (code "191") (name "unconnected-(P1C-44-PadC-44)") (class "Default")
      (node (ref "P1") (pin "C-44") (pinfunction "44_C-44") (pintype "input+no_connect"))
    )
    (net (code "192") (name "unconnected-(P1C-45-PadC-45)") (class "Default")
      (node (ref "P1") (pin "C-45") (pinfunction "45_C-45") (pintype "input+no_connect"))
    )
    (net (code "193") (name "unconnected-(P1C-46-PadC-46)") (class "Default")
      (node (ref "P1") (pin "C-46") (pinfunction "46_C-46") (pintype "input+no_connect"))
    )
    (net (code "194") (name "unconnected-(P1C-47-PadC-47)") (class "Default")
      (node (ref "P1") (pin "C-47") (pinfunction "47_C-47") (pintype "input+no_connect"))
    )
    (net (code "195") (name "unconnected-(P1C-48-PadC-48)") (class "Default")
      (node (ref "P1") (pin "C-48") (pinfunction "48_C-48") (pintype "input+no_connect"))
    )
    (net (code "196") (name "unconnected-(P1C-51-PadC-51)") (class "Default")
      (node (ref "P1") (pin "C-51") (pinfunction "51_C-51") (pintype "input"))
    )
    (net (code "197") (name "unconnected-(P1C-52-PadC-52)") (class "Default")
      (node (ref "P1") (pin "C-52") (pinfunction "52_C-52") (pintype "input+no_connect"))
    )
    (net (code "198") (name "unconnected-(P1C-53-PadC-53)") (class "Default")
      (node (ref "P1") (pin "C-53") (pinfunction "53_C-53") (pintype "input+no_connect"))
    )
    (net (code "199") (name "unconnected-(P1C-54-PadC-54)") (class "Default")
      (node (ref "P1") (pin "C-54") (pinfunction "54_C-54") (pintype "input+no_connect"))
    )
    (net (code "200") (name "unconnected-(P1C-55-PadC-55)") (class "Default")
      (node (ref "P1") (pin "C-55") (pinfunction "55_C-55") (pintype "input+no_connect"))
    )
    (net (code "201") (name "unconnected-(P1C-56-PadC-56)") (class "Default")
      (node (ref "P1") (pin "C-56") (pinfunction "56_C-56") (pintype "input+no_connect"))
    )
    (net (code "202") (name "unconnected-(P1C-57-PadC-57)") (class "Default")
      (node (ref "P1") (pin "C-57") (pinfunction "57_C-57") (pintype "input+no_connect"))
    )
    (net (code "203") (name "unconnected-(P1C-58-PadC-58)") (class "Default")
      (node (ref "P1") (pin "C-58") (pinfunction "58_C-58") (pintype "input+no_connect"))
    )
    (net (code "204") (name "unconnected-(P1C-61-PadC-61)") (class "Default")
      (node (ref "P1") (pin "C-61") (pinfunction "61_C-61") (pintype "input+no_connect"))
    )
    (net (code "205") (name "unconnected-(P1C-62-PadC-62)") (class "Default")
      (node (ref "P1") (pin "C-62") (pinfunction "62_C-62") (pintype "input+no_connect"))
    )
    (net (code "206") (name "unconnected-(P1C-63-PadC-63)") (class "Default")
      (node (ref "P1") (pin "C-63") (pinfunction "63_C-63") (pintype "input+no_connect"))
    )
    (net (code "207") (name "unconnected-(P1C-64-PadC-64)") (class "Default")
      (node (ref "P1") (pin "C-64") (pinfunction "64_C-64") (pintype "input+no_connect"))
    )
    (net (code "208") (name "unconnected-(P1C-65-PadC-65)") (class "Default")
      (node (ref "P1") (pin "C-65") (pinfunction "65_C-65") (pintype "input+no_connect"))
    )
    (net (code "209") (name "unconnected-(P1C-66-PadC-66)") (class "Default")
      (node (ref "P1") (pin "C-66") (pinfunction "66_C-66") (pintype "input+no_connect"))
    )
    (net (code "210") (name "unconnected-(P1C-67-PadC-67)") (class "Default")
      (node (ref "P1") (pin "C-67") (pinfunction "67_C-67") (pintype "input+no_connect"))
    )
    (net (code "211") (name "unconnected-(P1C-68-PadC-68)") (class "Default")
      (node (ref "P1") (pin "C-68") (pinfunction "68_C-68") (pintype "input+no_connect"))
    )
    (net (code "212") (name "unconnected-(P1C-71-PadC-71)") (class "Default")
      (node (ref "P1") (pin "C-71") (pinfunction "71_C-71") (pintype "input+no_connect"))
    )
    (net (code "213") (name "unconnected-(P1C-72-PadC-72)") (class "Default")
      (node (ref "P1") (pin "C-72") (pinfunction "72_C-72") (pintype "input+no_connect"))
    )
    (net (code "214") (name "unconnected-(P1C-73-PadC-73)") (class "Default")
      (node (ref "P1") (pin "C-73") (pinfunction "73_C-73") (pintype "input+no_connect"))
    )
    (net (code "215") (name "unconnected-(P1C-74-PadC-74)") (class "Default")
      (node (ref "P1") (pin "C-74") (pinfunction "74_C-74") (pintype "input+no_connect"))
    )
    (net (code "216") (name "unconnected-(P1C-75-PadC-75)") (class "Default")
      (node (ref "P1") (pin "C-75") (pinfunction "75_C-75") (pintype "input+no_connect"))
    )
    (net (code "217") (name "unconnected-(P1C-76-PadC-76)") (class "Default")
      (node (ref "P1") (pin "C-76") (pinfunction "76_C-76") (pintype "input+no_connect"))
    )
    (net (code "218") (name "unconnected-(P1C-81-PadC-81)") (class "Default")
      (node (ref "P1") (pin "C-81") (pinfunction "81_C-81") (pintype "input+no_connect"))
    )
    (net (code "219") (name "unconnected-(P1C-82-PadC-82)") (class "Default")
      (node (ref "P1") (pin "C-82") (pinfunction "82_C-82") (pintype "input+no_connect"))
    )
    (net (code "220") (name "unconnected-(P1C-83-PadC-83)") (class "Default")
      (node (ref "P1") (pin "C-83") (pinfunction "83_C-83") (pintype "input+no_connect"))
    )
    (net (code "221") (name "unconnected-(P1C-84-PadC-84)") (class "Default")
      (node (ref "P1") (pin "C-84") (pinfunction "84_C-84") (pintype "input+no_connect"))
    )
    (net (code "222") (name "unconnected-(P1D-1-PadD-1)") (class "Default")
      (node (ref "P1") (pin "D-1") (pinfunction "1_D-1") (pintype "input+no_connect"))
    )
    (net (code "223") (name "unconnected-(P1D-2-PadD-2)") (class "Default")
      (node (ref "P1") (pin "D-2") (pinfunction "2_D-2") (pintype "input+no_connect"))
    )
    (net (code "224") (name "unconnected-(P1D-3-PadD-3)") (class "Default")
      (node (ref "P1") (pin "D-3") (pinfunction "3_D-3") (pintype "input+no_connect"))
    )
    (net (code "225") (name "unconnected-(P1D-4-PadD-4)") (class "Default")
      (node (ref "P1") (pin "D-4") (pinfunction "4_D-4") (pintype "input+no_connect"))
    )
    (net (code "226") (name "unconnected-(P1D-5-PadD-5)") (class "Default")
      (node (ref "P1") (pin "D-5") (pinfunction "5_D-5") (pintype "input+no_connect"))
    )
    (net (code "227") (name "unconnected-(P1D-6-PadD-6)") (class "Default")
      (node (ref "P1") (pin "D-6") (pinfunction "6_D-6") (pintype "input+no_connect"))
    )
    (net (code "228") (name "unconnected-(P1D-7-PadD-7)") (class "Default")
      (node (ref "P1") (pin "D-7") (pinfunction "7_D-7") (pintype "input+no_connect"))
    )
    (net (code "229") (name "unconnected-(P1D-8-PadD-8)") (class "Default")
      (node (ref "P1") (pin "D-8") (pinfunction "8_D-8") (pintype "input+no_connect"))
    )
    (net (code "230") (name "unconnected-(P1D-11-PadD-11)") (class "Default")
      (node (ref "P1") (pin "D-11") (pinfunction "11_D-11") (pintype "input+no_connect"))
    )
    (net (code "231") (name "unconnected-(P1D-13-PadD-13)") (class "Default")
      (node (ref "P1") (pin "D-13") (pinfunction "13_D-13") (pintype "input+no_connect"))
    )
    (net (code "232") (name "unconnected-(P1D-16-PadD-16)") (class "Default")
      (node (ref "P1") (pin "D-16") (pinfunction "16_D-16") (pintype "input+no_connect"))
    )
    (net (code "233") (name "unconnected-(P1D-22-PadD-22)") (class "Default")
      (node (ref "P1") (pin "D-22") (pinfunction "22_D-22") (pintype "input+no_connect"))
    )
    (net (code "234") (name "unconnected-(P1D-28-PadD-28)") (class "Default")
      (node (ref "P1") (pin "D-28") (pinfunction "28_D-28") (pintype "input+no_connect"))
    )
    (net (code "235") (name "unconnected-(P1D-34-PadD-34)") (class "Default")
      (node (ref "P1") (pin "D-34") (pinfunction "34_D-34") (pintype "input+no_connect"))
    )
    (net (code "236") (name "unconnected-(P1D-41-PadD-41)") (class "Default")
      (node (ref "P1") (pin "D-41") (pinfunction "41_D-41") (pintype "input+no_connect"))
    )
    (net (code "237") (name "unconnected-(P1D-42-PadD-42)") (class "Default")
      (node (ref "P1") (pin "D-42") (pinfunction "42_D-42") (pintype "input+no_connect"))
    )
    (net (code "238") (name "unconnected-(P1D-43-PadD-43)") (class "Default")
      (node (ref "P1") (pin "D-43") (pinfunction "43_D-43") (pintype "input+no_connect"))
    )
    (net (code "239") (name "unconnected-(P1D-44-PadD-44)") (class "Default")
      (node (ref "P1") (pin "D-44") (pinfunction "44_D-44") (pintype "input+no_connect"))
    )
    (net (code "240") (name "unconnected-(P1D-45-PadD-45)") (class "Default")
      (node (ref "P1") (pin "D-45") (pinfunction "45_D-45") (pintype "input+no_connect"))
    )
    (net (code "241") (name "unconnected-(P1D-46-PadD-46)") (class "Default")
      (node (ref "P1") (pin "D-46") (pinfunction "46_D-46") (pintype "input+no_connect"))
    )
    (net (code "242") (name "unconnected-(P1D-47-PadD-47)") (class "Default")
      (node (ref "P1") (pin "D-47") (pinfunction "47_D-47") (pintype "input+no_connect"))
    )
    (net (code "243") (name "unconnected-(P1D-48-PadD-48)") (class "Default")
      (node (ref "P1") (pin "D-48") (pinfunction "48_D-48") (pintype "input+no_connect"))
    )
    (net (code "244") (name "unconnected-(P1D-51-PadD-51)") (class "Default")
      (node (ref "P1") (pin "D-51") (pinfunction "51_D-51") (pintype "input+no_connect"))
    )
    (net (code "245") (name "unconnected-(P1D-52-PadD-52)") (class "Default")
      (node (ref "P1") (pin "D-52") (pinfunction "52_D-52") (pintype "input+no_connect"))
    )
    (net (code "246") (name "unconnected-(P1D-53-PadD-53)") (class "Default")
      (node (ref "P1") (pin "D-53") (pinfunction "53_D-53") (pintype "input+no_connect"))
    )
    (net (code "247") (name "unconnected-(P1D-54-PadD-54)") (class "Default")
      (node (ref "P1") (pin "D-54") (pinfunction "54_D-54") (pintype "input+no_connect"))
    )
    (net (code "248") (name "unconnected-(P1D-55-PadD-55)") (class "Default")
      (node (ref "P1") (pin "D-55") (pinfunction "55_D-55") (pintype "input+no_connect"))
    )
    (net (code "249") (name "unconnected-(P1D-56-PadD-56)") (class "Default")
      (node (ref "P1") (pin "D-56") (pinfunction "56_D-56") (pintype "input+no_connect"))
    )
    (net (code "250") (name "unconnected-(P1D-57-PadD-57)") (class "Default")
      (node (ref "P1") (pin "D-57") (pinfunction "57_D-57") (pintype "input+no_connect"))
    )
    (net (code "251") (name "unconnected-(P1D-58-PadD-58)") (class "Default")
      (node (ref "P1") (pin "D-58") (pinfunction "58_D-58") (pintype "input+no_connect"))
    )
    (net (code "252") (name "unconnected-(P1D-61-PadD-61)") (class "Default")
      (node (ref "P1") (pin "D-61") (pinfunction "61_D-61") (pintype "input+no_connect"))
    )
    (net (code "253") (name "unconnected-(P1D-62-PadD-62)") (class "Default")
      (node (ref "P1") (pin "D-62") (pinfunction "62_D-62") (pintype "input+no_connect"))
    )
    (net (code "254") (name "unconnected-(P1D-63-PadD-63)") (class "Default")
      (node (ref "P1") (pin "D-63") (pinfunction "63_D-63") (pintype "input+no_connect"))
    )
    (net (code "255") (name "unconnected-(P1D-64-PadD-64)") (class "Default")
      (node (ref "P1") (pin "D-64") (pinfunction "64_D-64") (pintype "input+no_connect"))
    )
    (net (code "256") (name "unconnected-(P1D-65-PadD-65)") (class "Default")
      (node (ref "P1") (pin "D-65") (pinfunction "65_D-65") (pintype "input+no_connect"))
    )
    (net (code "257") (name "unconnected-(P1D-66-PadD-66)") (class "Default")
      (node (ref "P1") (pin "D-66") (pinfunction "66_D-66") (pintype "input+no_connect"))
    )
    (net (code "258") (name "unconnected-(P1D-67-PadD-67)") (class "Default")
      (node (ref "P1") (pin "D-67") (pinfunction "67_D-67") (pintype "input+no_connect"))
    )
    (net (code "259") (name "unconnected-(P1D-68-PadD-68)") (class "Default")
      (node (ref "P1") (pin "D-68") (pinfunction "68_D-68") (pintype "input+no_connect"))
    )
    (net (code "260") (name "unconnected-(P1D-71-PadD-71)") (class "Default")
      (node (ref "P1") (pin "D-71") (pinfunction "71_D-71") (pintype "input+no_connect"))
    )
    (net (code "261") (name "unconnected-(P1D-72-PadD-72)") (class "Default")
      (node (ref "P1") (pin "D-72") (pinfunction "72_D-72") (pintype "input+no_connect"))
    )
    (net (code "262") (name "unconnected-(P1D-73-PadD-73)") (class "Default")
      (node (ref "P1") (pin "D-73") (pinfunction "73_D-73") (pintype "input+no_connect"))
    )
    (net (code "263") (name "unconnected-(P1D-74-PadD-74)") (class "Default")
      (node (ref "P1") (pin "D-74") (pinfunction "74_D-74") (pintype "input+no_connect"))
    )
    (net (code "264") (name "unconnected-(P1D-75-PadD-75)") (class "Default")
      (node (ref "P1") (pin "D-75") (pinfunction "75_D-75") (pintype "input+no_connect"))
    )
    (net (code "265") (name "unconnected-(P1D-76-PadD-76)") (class "Default")
      (node (ref "P1") (pin "D-76") (pinfunction "76_D-76") (pintype "input+no_connect"))
    )
    (net (code "266") (name "unconnected-(P1D-77-PadD-77)") (class "Default")
      (node (ref "P1") (pin "D-77") (pinfunction "77_D-77") (pintype "input+no_connect"))
    )
    (net (code "267") (name "unconnected-(P1D-78-PadD-78)") (class "Default")
      (node (ref "P1") (pin "D-78") (pinfunction "78_D-78") (pintype "input+no_connect"))
    )
    (net (code "268") (name "unconnected-(P1D-79-PadD-79)") (class "Default")
      (node (ref "P1") (pin "D-79") (pinfunction "79_D-79") (pintype "input+no_connect"))
    )
    (net (code "269") (name "unconnected-(P1D-80-PadD-80)") (class "Default")
      (node (ref "P1") (pin "D-80") (pinfunction "80_D-80") (pintype "input+no_connect"))
    )
    (net (code "270") (name "unconnected-(P1D-81-PadD-81)") (class "Default")
      (node (ref "P1") (pin "D-81") (pinfunction "81_D-81") (pintype "input+no_connect"))
    )
    (net (code "271") (name "unconnected-(P1D-82-PadD-82)") (class "Default")
      (node (ref "P1") (pin "D-82") (pinfunction "82_D-82") (pintype "input+no_connect"))
    )
    (net (code "272") (name "unconnected-(P1D-83-PadD-83)") (class "Default")
      (node (ref "P1") (pin "D-83") (pinfunction "83_D-83") (pintype "input+no_connect"))
    )
    (net (code "273") (name "unconnected-(P1D-84-PadD-84)") (class "Default")
      (node (ref "P1") (pin "D-84") (pinfunction "84_D-84") (pintype "input+no_connect"))
    )
  )
)
